# optocopler_adapter.net
KiCad netlist of a schematic drawn in EAGLE
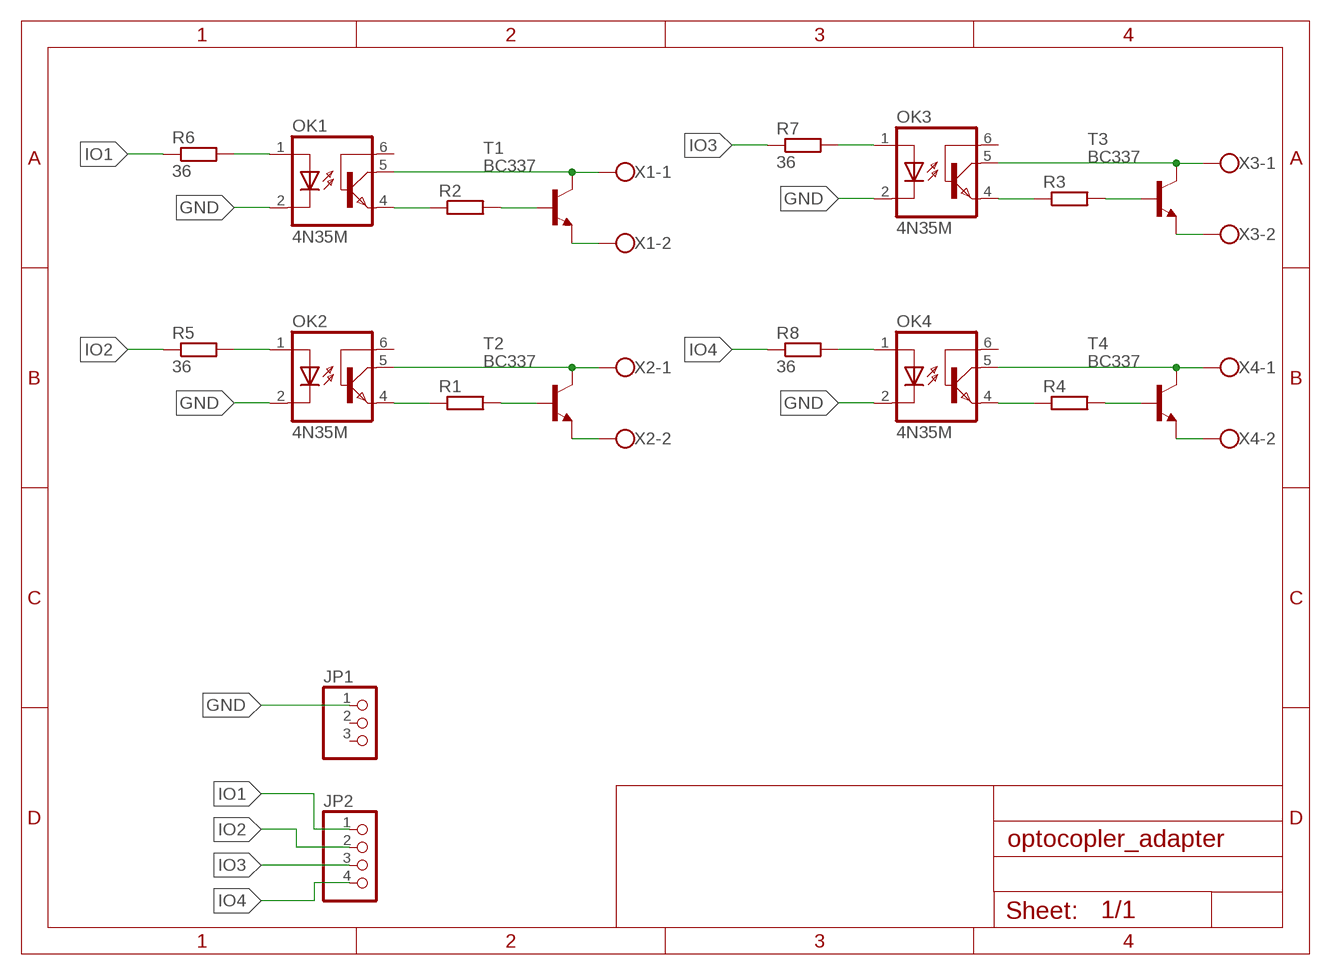
[diagram p0: schematic, sheet 1]

(export (version "E")
  (design (tool "Eeschema 10.0.6"))
  (components
    (comp (ref "JP1")
      (value "PINHD-1X3/90")
      (footprint "eagle-import:1X03_90")
      (libsource (lib "eagle-import") (part "PINHD-1X3/90"))
    )
    (comp (ref "JP2")
      (value "PINHD-1X4/90")
      (footprint "eagle-import:1X04_90")
      (libsource (lib "eagle-import") (part "PINHD-1X4/90"))
    )
    (comp (ref "OK1")
      (value "4N35M")
      (footprint "eagle-import:DIL06")
      (fields (field (name "MPN") "4N35-M"))
      (libsource (lib "eagle-import") (part "4N?M35"))
    )
    (comp (ref "OK2")
      (value "4N35M")
      (footprint "eagle-import:DIL06")
      (fields (field (name "MPN") "4N35-M"))
      (libsource (lib "eagle-import") (part "4N?M35"))
    )
    (comp (ref "OK3")
      (value "4N35M")
      (footprint "eagle-import:DIL06")
      (fields (field (name "MPN") "4N35-M"))
      (libsource (lib "eagle-import") (part "4N?M35"))
    )
    (comp (ref "OK4")
      (value "4N35M")
      (footprint "eagle-import:DIL06")
      (fields (field (name "MPN") "4N35-M"))
      (libsource (lib "eagle-import") (part "4N?M35"))
    )
    (comp (ref "R1")
      (value "R-EU_0204/7")
      (footprint "eagle-import:0204_7")
      (libsource (lib "eagle-import") (part "R-EU_0204/7"))
    )
    (comp (ref "R2")
      (value "R-EU_0204/7")
      (footprint "eagle-import:0204_7")
      (libsource (lib "eagle-import") (part "R-EU_0204/7"))
    )
    (comp (ref "R3")
      (value "R-EU_0204/7")
      (footprint "eagle-import:0204_7")
      (libsource (lib "eagle-import") (part "R-EU_0204/7"))
    )
    (comp (ref "R4")
      (value "R-EU_0204/7")
      (footprint "eagle-import:0204_7")
      (libsource (lib "eagle-import") (part "R-EU_0204/7"))
    )
    (comp (ref "R5")
      (value "36")
      (footprint "eagle-import:0204_7")
      (libsource (lib "eagle-import") (part "R-EU_0204/7"))
    )
    (comp (ref "R6")
      (value "36")
      (footprint "eagle-import:0204_7")
      (libsource (lib "eagle-import") (part "R-EU_0204/7"))
    )
    (comp (ref "R7")
      (value "36")
      (footprint "eagle-import:0204_7")
      (libsource (lib "eagle-import") (part "R-EU_0204/7"))
    )
    (comp (ref "R8")
      (value "36")
      (footprint "eagle-import:0204_7")
      (libsource (lib "eagle-import") (part "R-EU_0204/7"))
    )
    (comp (ref "T1")
      (value "BC337")
      (footprint "eagle-import:TO92")
      (libsource (lib "eagle-import") (part "-NPN-TO92"))
    )
    (comp (ref "T2")
      (value "BC337")
      (footprint "eagle-import:TO92")
      (libsource (lib "eagle-import") (part "-NPN-TO92"))
    )
    (comp (ref "T3")
      (value "BC337")
      (footprint "eagle-import:TO92")
      (libsource (lib "eagle-import") (part "-NPN-TO92"))
    )
    (comp (ref "T4")
      (value "BC337")
      (footprint "eagle-import:TO92")
      (libsource (lib "eagle-import") (part "-NPN-TO92"))
    )
    (comp (ref "X1")
      (value "W237-102")
      (footprint "eagle-import:W237-102")
      (fields (field (name "MPN") "237-102"))
      (libsource (lib "eagle-import") (part "W237-102"))
    )
    (comp (ref "X2")
      (value "W237-102")
      (footprint "eagle-import:W237-102")
      (fields (field (name "MPN") "237-102"))
      (libsource (lib "eagle-import") (part "W237-102"))
    )
    (comp (ref "X3")
      (value "W237-102")
      (footprint "eagle-import:W237-102")
      (fields (field (name "MPN") "237-102"))
      (libsource (lib "eagle-import") (part "W237-102"))
    )
    (comp (ref "X4")
      (value "W237-102")
      (footprint "eagle-import:W237-102")
      (fields (field (name "MPN") "237-102"))
      (libsource (lib "eagle-import") (part "W237-102"))
    )
  )
  (nets
    (net (code "1") (name "GND") (class "Default")
      (node (ref "JP1") (pin "1") (pinfunction "1_1") (pintype "passive"))
      (node (ref "OK1") (pin "2") (pinfunction "C_2") (pintype "passive"))
      (node (ref "OK2") (pin "2") (pinfunction "C_2") (pintype "passive"))
      (node (ref "OK3") (pin "2") (pinfunction "C_2") (pintype "passive"))
      (node (ref "OK4") (pin "2") (pinfunction "C_2") (pintype "passive"))
    )
    (net (code "2") (name "IO1") (class "Default")
      (node (ref "JP2") (pin "1") (pinfunction "1_1") (pintype "passive"))
      (node (ref "R6") (pin "1") (pinfunction "1_1") (pintype "passive"))
    )
    (net (code "3") (name "IO2") (class "Default")
      (node (ref "JP2") (pin "2") (pinfunction "2_2") (pintype "passive"))
      (node (ref "R5") (pin "1") (pinfunction "1_1") (pintype "passive"))
    )
    (net (code "4") (name "IO3") (class "Default")
      (node (ref "JP2") (pin "3") (pinfunction "3_3") (pintype "passive"))
      (node (ref "R7") (pin "1") (pinfunction "1_1") (pintype "passive"))
    )
    (net (code "5") (name "IO4") (class "Default")
      (node (ref "JP2") (pin "4") (pinfunction "4_4") (pintype "passive"))
      (node (ref "R8") (pin "1") (pinfunction "1_1") (pintype "passive"))
    )
    (net (code "6") (name "Net-(OK1-A)") (class "Default")
      (node (ref "OK1") (pin "1") (pinfunction "A_1") (pintype "passive"))
      (node (ref "R6") (pin "2") (pinfunction "2_2") (pintype "passive"))
    )
    (net (code "7") (name "Net-(OK1-COL)") (class "Default")
      (node (ref "OK1") (pin "5") (pinfunction "COL_5") (pintype "passive"))
      (node (ref "T1") (pin "3") (pinfunction "C_3") (pintype "passive"))
      (node (ref "X1") (pin "1") (pinfunction "KL_1") (pintype "passive"))
    )
    (net (code "8") (name "Net-(OK1-EMI)") (class "Default")
      (node (ref "OK1") (pin "4") (pinfunction "EMI_4") (pintype "passive"))
      (node (ref "R2") (pin "1") (pinfunction "1_1") (pintype "passive"))
    )
    (net (code "9") (name "Net-(OK2-A)") (class "Default")
      (node (ref "OK2") (pin "1") (pinfunction "A_1") (pintype "passive"))
      (node (ref "R5") (pin "2") (pinfunction "2_2") (pintype "passive"))
    )
    (net (code "10") (name "Net-(OK2-COL)") (class "Default")
      (node (ref "OK2") (pin "5") (pinfunction "COL_5") (pintype "passive"))
      (node (ref "T2") (pin "3") (pinfunction "C_3") (pintype "passive"))
      (node (ref "X2") (pin "1") (pinfunction "KL_1") (pintype "passive"))
    )
    (net (code "11") (name "Net-(OK2-EMI)") (class "Default")
      (node (ref "OK2") (pin "4") (pinfunction "EMI_4") (pintype "passive"))
      (node (ref "R1") (pin "1") (pinfunction "1_1") (pintype "passive"))
    )
    (net (code "12") (name "Net-(OK3-A)") (class "Default")
      (node (ref "OK3") (pin "1") (pinfunction "A_1") (pintype "passive"))
      (node (ref "R7") (pin "2") (pinfunction "2_2") (pintype "passive"))
    )
    (net (code "13") (name "Net-(OK3-COL)") (class "Default")
      (node (ref "OK3") (pin "5") (pinfunction "COL_5") (pintype "passive"))
      (node (ref "T3") (pin "3") (pinfunction "C_3") (pintype "passive"))
      (node (ref "X3") (pin "1") (pinfunction "KL_1") (pintype "passive"))
    )
    (net (code "14") (name "Net-(OK3-EMI)") (class "Default")
      (node (ref "OK3") (pin "4") (pinfunction "EMI_4") (pintype "passive"))
      (node (ref "R3") (pin "1") (pinfunction "1_1") (pintype "passive"))
    )
    (net (code "15") (name "Net-(OK4-A)") (class "Default")
      (node (ref "OK4") (pin "1") (pinfunction "A_1") (pintype "passive"))
      (node (ref "R8") (pin "2") (pinfunction "2_2") (pintype "passive"))
    )
    (net (code "16") (name "Net-(OK4-COL)") (class "Default")
      (node (ref "OK4") (pin "5") (pinfunction "COL_5") (pintype "passive"))
      (node (ref "T4") (pin "3") (pinfunction "C_3") (pintype "passive"))
      (node (ref "X4") (pin "1") (pinfunction "KL_1") (pintype "passive"))
    )
    (net (code "17") (name "Net-(OK4-EMI)") (class "Default")
      (node (ref "OK4") (pin "4") (pinfunction "EMI_4") (pintype "passive"))
      (node (ref "R4") (pin "1") (pinfunction "1_1") (pintype "passive"))
    )
    (net (code "18") (name "Net-(T1-B)") (class "Default")
      (node (ref "R2") (pin "2") (pinfunction "2_2") (pintype "passive"))
      (node (ref "T1") (pin "2") (pinfunction "B_2") (pintype "passive"))
    )
    (net (code "19") (name "Net-(T1-E)") (class "Default")
      (node (ref "T1") (pin "1") (pinfunction "E_1") (pintype "passive"))
      (node (ref "X1") (pin "2") (pinfunction "KL_2") (pintype "passive"))
    )
    (net (code "20") (name "Net-(T2-B)") (class "Default")
      (node (ref "R1") (pin "2") (pinfunction "2_2") (pintype "passive"))
      (node (ref "T2") (pin "2") (pinfunction "B_2") (pintype "passive"))
    )
    (net (code "21") (name "Net-(T2-E)") (class "Default")
      (node (ref "T2") (pin "1") (pinfunction "E_1") (pintype "passive"))
      (node (ref "X2") (pin "2") (pinfunction "KL_2") (pintype "passive"))
    )
    (net (code "22") (name "Net-(T3-B)") (class "Default")
      (node (ref "R3") (pin "2") (pinfunction "2_2") (pintype "passive"))
      (node (ref "T3") (pin "2") (pinfunction "B_2") (pintype "passive"))
    )
    (net (code "23") (name "Net-(T3-E)") (class "Default")
      (node (ref "T3") (pin "1") (pinfunction "E_1") (pintype "passive"))
      (node (ref "X3") (pin "2") (pinfunction "KL_2") (pintype "passive"))
    )
    (net (code "24") (name "Net-(T4-B)") (class "Default")
      (node (ref "R4") (pin "2") (pinfunction "2_2") (pintype "passive"))
      (node (ref "T4") (pin "2") (pinfunction "B_2") (pintype "passive"))
    )
    (net (code "25") (name "Net-(T4-E)") (class "Default")
      (node (ref "T4") (pin "1") (pinfunction "E_1") (pintype "passive"))
      (node (ref "X4") (pin "2") (pinfunction "KL_2") (pintype "passive"))
    )
    (net (code "26") (name "unconnected-(JP1-Pad2)") (class "Default")
      (node (ref "JP1") (pin "2") (pinfunction "2_2") (pintype "passive"))
    )
    (net (code "27") (name "unconnected-(JP1-Pad3)") (class "Default")
      (node (ref "JP1") (pin "3") (pinfunction "3_3") (pintype "passive"))
    )
    (net (code "28") (name "unconnected-(OK1-BAS-Pad6)") (class "Default")
      (node (ref "OK1") (pin "6") (pinfunction "BAS_6") (pintype "passive"))
    )
    (net (code "29") (name "unconnected-(OK2-BAS-Pad6)") (class "Default")
      (node (ref "OK2") (pin "6") (pinfunction "BAS_6") (pintype "passive"))
    )
    (net (code "30") (name "unconnected-(OK3-BAS-Pad6)") (class "Default")
      (node (ref "OK3") (pin "6") (pinfunction "BAS_6") (pintype "passive"))
    )
    (net (code "31") (name "unconnected-(OK4-BAS-Pad6)") (class "Default")
      (node (ref "OK4") (pin "6") (pinfunction "BAS_6") (pintype "passive"))
    )
  )
)
